# Cursor-Internal.net
KiCad netlist of a schematic drawn in EAGLE
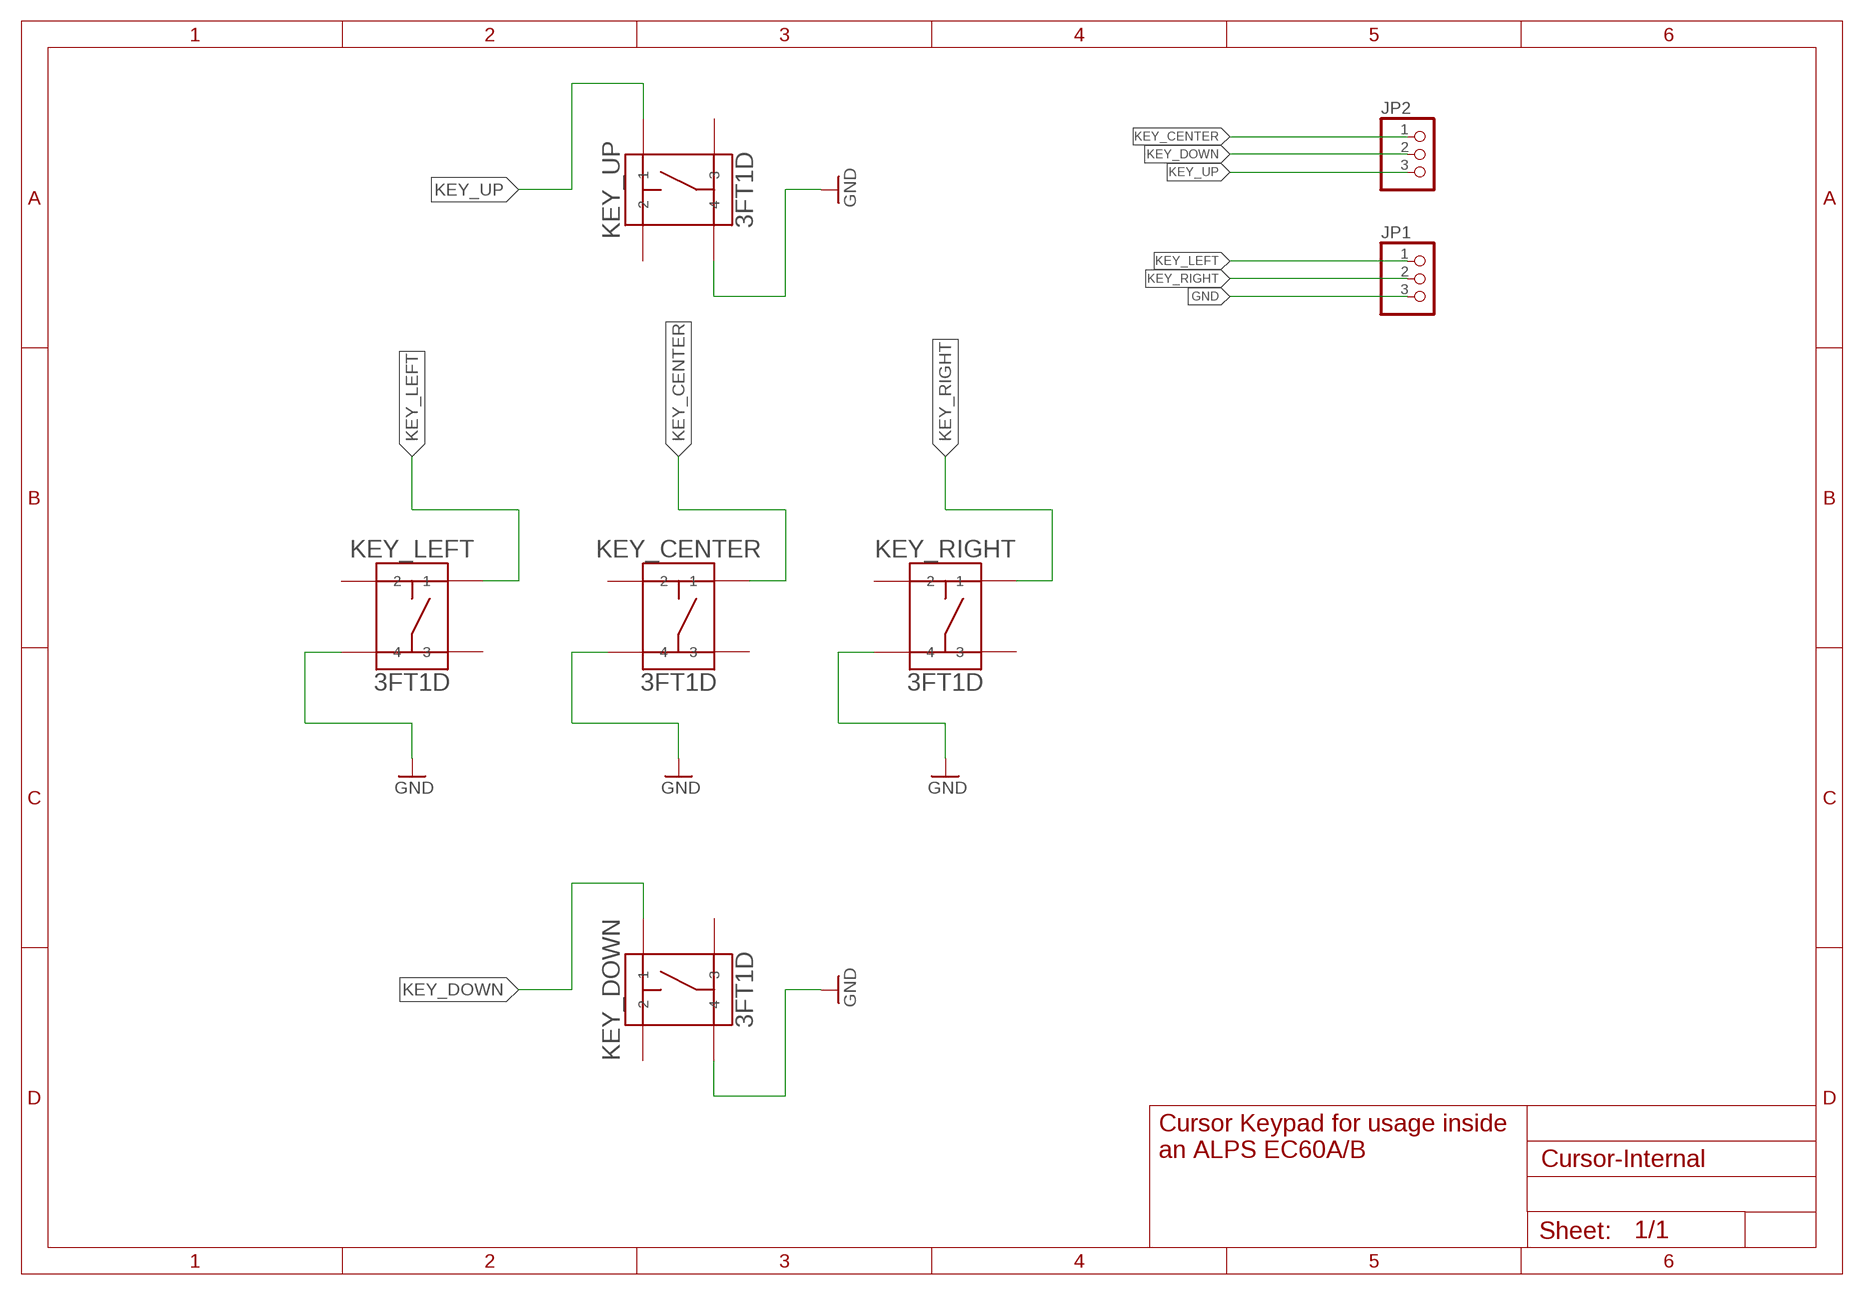
[diagram p0: schematic, sheet 1]

(export (version "E")
  (design (tool "Eeschema 10.0.6"))
  (components
    (comp (ref "JP1")
      (value "PINHD-1X3")
      (footprint "eagle-import:1X03")
      (libsource (lib "eagle-import") (part "PINHD-1X3"))
    )
    (comp (ref "JP2")
      (value "PINHD-1X3")
      (footprint "eagle-import:1X03")
      (libsource (lib "eagle-import") (part "PINHD-1X3"))
    )
    (comp (ref "KEY_CENTER")
      (value "3FT1D")
      (footprint "eagle-import:3FT")
      (libsource (lib "eagle-import") (part "3FT1D"))
    )
    (comp (ref "KEY_DOWN")
      (value "3FT1D")
      (footprint "eagle-import:3FT")
      (libsource (lib "eagle-import") (part "3FT1D"))
    )
    (comp (ref "KEY_LEFT")
      (value "3FT1D")
      (footprint "eagle-import:3FT")
      (libsource (lib "eagle-import") (part "3FT1D"))
    )
    (comp (ref "KEY_RIGHT")
      (value "3FT1D")
      (footprint "eagle-import:3FT")
      (libsource (lib "eagle-import") (part "3FT1D"))
    )
    (comp (ref "KEY_UP")
      (value "3FT1D")
      (footprint "eagle-import:3FT")
      (libsource (lib "eagle-import") (part "3FT1D"))
    )
  )
  (nets
    (net (code "1") (name "GND") (class "Default")
      (node (ref "JP1") (pin "3") (pinfunction "3_3") (pintype "passive"))
      (node (ref "KEY_CENTER") (pin "P$4") (pinfunction "4_P$4") (pintype "bidirectional"))
      (node (ref "KEY_DOWN") (pin "P$4") (pinfunction "4_P$4") (pintype "bidirectional"))
      (node (ref "KEY_LEFT") (pin "P$4") (pinfunction "4_P$4") (pintype "bidirectional"))
      (node (ref "KEY_RIGHT") (pin "P$4") (pinfunction "4_P$4") (pintype "bidirectional"))
      (node (ref "KEY_UP") (pin "P$4") (pinfunction "4_P$4") (pintype "bidirectional"))
    )
    (net (code "2") (name "KEY_CENTER") (class "Default")
      (node (ref "JP2") (pin "1") (pinfunction "1_1") (pintype "passive"))
      (node (ref "KEY_CENTER") (pin "P$1") (pinfunction "1_P$1") (pintype "bidirectional"))
    )
    (net (code "3") (name "KEY_DOWN") (class "Default")
      (node (ref "JP2") (pin "2") (pinfunction "2_2") (pintype "passive"))
      (node (ref "KEY_DOWN") (pin "P$1") (pinfunction "1_P$1") (pintype "bidirectional"))
    )
    (net (code "4") (name "KEY_LEFT") (class "Default")
      (node (ref "JP1") (pin "1") (pinfunction "1_1") (pintype "passive"))
      (node (ref "KEY_LEFT") (pin "P$1") (pinfunction "1_P$1") (pintype "bidirectional"))
    )
    (net (code "5") (name "KEY_RIGHT") (class "Default")
      (node (ref "JP1") (pin "2") (pinfunction "2_2") (pintype "passive"))
      (node (ref "KEY_RIGHT") (pin "P$1") (pinfunction "1_P$1") (pintype "bidirectional"))
    )
    (net (code "6") (name "KEY_UP") (class "Default")
      (node (ref "JP2") (pin "3") (pinfunction "3_3") (pintype "passive"))
      (node (ref "KEY_UP") (pin "P$1") (pinfunction "1_P$1") (pintype "bidirectional"))
    )
    (net (code "7") (name "unconnected-(KEY_CENTER-2-PadP$2)") (class "Default")
      (node (ref "KEY_CENTER") (pin "P$2") (pinfunction "2_P$2") (pintype "bidirectional"))
    )
    (net (code "8") (name "unconnected-(KEY_CENTER-3-PadP$3)") (class "Default")
      (node (ref "KEY_CENTER") (pin "P$3") (pinfunction "3_P$3") (pintype "bidirectional"))
    )
    (net (code "9") (name "unconnected-(KEY_DOWN-2-PadP$2)") (class "Default")
      (node (ref "KEY_DOWN") (pin "P$2") (pinfunction "2_P$2") (pintype "bidirectional"))
    )
    (net (code "10") (name "unconnected-(KEY_DOWN-3-PadP$3)") (class "Default")
      (node (ref "KEY_DOWN") (pin "P$3") (pinfunction "3_P$3") (pintype "bidirectional"))
    )
    (net (code "11") (name "unconnected-(KEY_LEFT-2-PadP$2)") (class "Default")
      (node (ref "KEY_LEFT") (pin "P$2") (pinfunction "2_P$2") (pintype "bidirectional"))
    )
    (net (code "12") (name "unconnected-(KEY_LEFT-3-PadP$3)") (class "Default")
      (node (ref "KEY_LEFT") (pin "P$3") (pinfunction "3_P$3") (pintype "bidirectional"))
    )
    (net (code "13") (name "unconnected-(KEY_RIGHT-2-PadP$2)") (class "Default")
      (node (ref "KEY_RIGHT") (pin "P$2") (pinfunction "2_P$2") (pintype "bidirectional"))
    )
    (net (code "14") (name "unconnected-(KEY_RIGHT-3-PadP$3)") (class "Default")
      (node (ref "KEY_RIGHT") (pin "P$3") (pinfunction "3_P$3") (pintype "bidirectional"))
    )
    (net (code "15") (name "unconnected-(KEY_UP-2-PadP$2)") (class "Default")
      (node (ref "KEY_UP") (pin "P$2") (pinfunction "2_P$2") (pintype "bidirectional"))
    )
    (net (code "16") (name "unconnected-(KEY_UP-3-PadP$3)") (class "Default")
      (node (ref "KEY_UP") (pin "P$3") (pinfunction "3_P$3") (pintype "bidirectional"))
    )
  )
)
